# Incubator.net
KiCad netlist of a schematic drawn in EAGLE
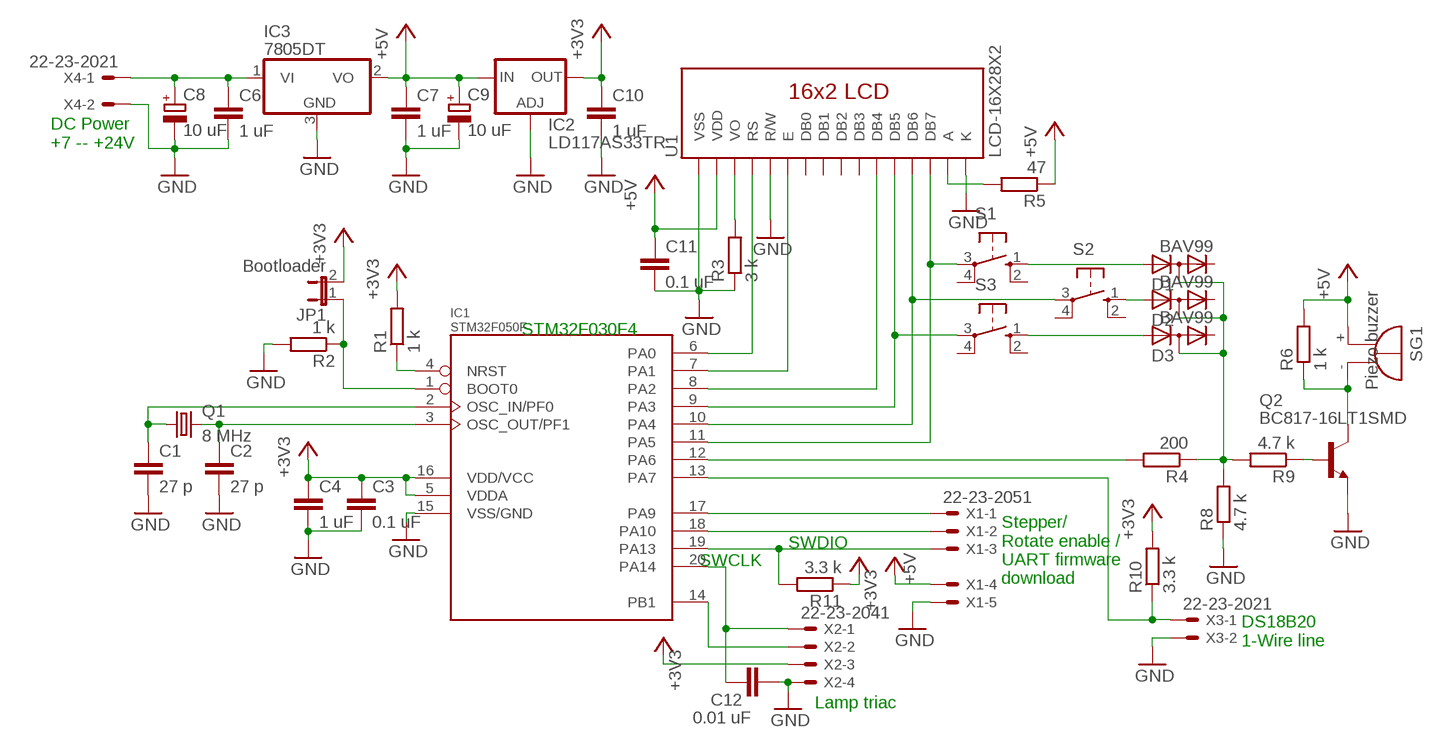
[diagram p0: schematic, sheet 1]

(export (version "E")
  (design (tool "Eeschema 10.0.6"))
  (components
    (comp (ref "C1")
      (value "27 p")
      (footprint "eagle-import:C0805")
      (libsource (lib "eagle-import") (part "C-EUC0805"))
    )
    (comp (ref "C2")
      (value "27 p")
      (footprint "eagle-import:C0805")
      (libsource (lib "eagle-import") (part "C-EUC0805"))
    )
    (comp (ref "C3")
      (value "0.1 uF")
      (footprint "eagle-import:C0805")
      (libsource (lib "eagle-import") (part "C-EUC0805"))
    )
    (comp (ref "C4")
      (value "1 uF")
      (footprint "eagle-import:C0805")
      (libsource (lib "eagle-import") (part "C-EUC0805"))
    )
    (comp (ref "C6")
      (value "1 uF")
      (footprint "eagle-import:C0805")
      (libsource (lib "eagle-import") (part "C-EUC0805"))
    )
    (comp (ref "C7")
      (value "1 uF")
      (footprint "eagle-import:C0805")
      (libsource (lib "eagle-import") (part "C-EUC0805"))
    )
    (comp (ref "C8")
      (value "10 uF")
      (footprint "eagle-import:TT2D4L")
      (libsource (lib "eagle-import") (part "CPOL-EUTT2D4L"))
    )
    (comp (ref "C9")
      (value "10 uF")
      (footprint "eagle-import:TT2D4L")
      (libsource (lib "eagle-import") (part "CPOL-EUTT2D4L"))
    )
    (comp (ref "C10")
      (value "1 uF")
      (footprint "eagle-import:C0805")
      (libsource (lib "eagle-import") (part "C-EUC0805"))
    )
    (comp (ref "C11")
      (value "0.1 uF")
      (footprint "eagle-import:C0805")
      (libsource (lib "eagle-import") (part "C-EUC0805"))
    )
    (comp (ref "C12")
      (value "0.01 uF")
      (footprint "eagle-import:C0805")
      (libsource (lib "eagle-import") (part "C-EUC0805"))
    )
    (comp (ref "D1")
      (value "BAV99")
      (footprint "eagle-import:SOT23")
      (libsource (lib "eagle-import") (part "BAV199"))
    )
    (comp (ref "D2")
      (value "BAV99")
      (footprint "eagle-import:SOT23")
      (libsource (lib "eagle-import") (part "BAV199"))
    )
    (comp (ref "D3")
      (value "BAV99")
      (footprint "eagle-import:SOT23")
      (libsource (lib "eagle-import") (part "BAV199"))
    )
    (comp (ref "IC1")
      (value "STM32F050F")
      (footprint "eagle-import:TSSOP20")
      (libsource (lib "eagle-import") (part "STM32F050F"))
    )
    (comp (ref "IC2")
      (value "LD117AS33TR")
      (footprint "eagle-import:SOT223")
      (libsource (lib "eagle-import") (part "LD117A?S33TR"))
    )
    (comp (ref "IC3")
      (value "7805DT")
      (footprint "eagle-import:TO252")
      (libsource (lib "eagle-import") (part "78DT05"))
    )
    (comp (ref "JP1")
      (value "Bootloader")
      (footprint "eagle-import:JP1")
      (libsource (lib "eagle-import") (part "JP1E"))
    )
    (comp (ref "Q1")
      (value "8 MHz")
      (footprint "eagle-import:HC49_S")
      (libsource (lib "eagle-import") (part "CRYSTALHC49S"))
    )
    (comp (ref "Q2")
      (value "BC817-16LT1SMD")
      (footprint "eagle-import:SOT23-BEC")
      (libsource (lib "eagle-import") (part "BC817SMD-16LT1"))
    )
    (comp (ref "R1")
      (value "1 k")
      (footprint "eagle-import:R0805")
      (libsource (lib "eagle-import") (part "R-EU_R0805"))
    )
    (comp (ref "R2")
      (value "1 k")
      (footprint "eagle-import:R0805")
      (libsource (lib "eagle-import") (part "R-EU_R0805"))
    )
    (comp (ref "R3")
      (value "3 k")
      (footprint "eagle-import:R0805")
      (libsource (lib "eagle-import") (part "R-EU_R0805"))
    )
    (comp (ref "R4")
      (value "200")
      (footprint "eagle-import:R0805")
      (libsource (lib "eagle-import") (part "R-EU_R0805"))
    )
    (comp (ref "R5")
      (value "47")
      (footprint "eagle-import:R0805")
      (libsource (lib "eagle-import") (part "R-EU_R0805"))
    )
    (comp (ref "R6")
      (value "1 k")
      (footprint "eagle-import:R0805")
      (libsource (lib "eagle-import") (part "R-EU_R0805"))
    )
    (comp (ref "R8")
      (value "4.7 k")
      (footprint "eagle-import:R0805")
      (libsource (lib "eagle-import") (part "R-EU_R0805"))
    )
    (comp (ref "R9")
      (value "4.7 k")
      (footprint "eagle-import:R0805")
      (libsource (lib "eagle-import") (part "R-EU_R0805"))
    )
    (comp (ref "R10")
      (value "3.3 k")
      (footprint "eagle-import:R0805")
      (libsource (lib "eagle-import") (part "R-EU_R0805"))
    )
    (comp (ref "R11")
      (value "3.3 k")
      (footprint "eagle-import:R0805")
      (libsource (lib "eagle-import") (part "R-EU_R0805"))
    )
    (comp (ref "S1")
      (value "10-XX")
      (footprint "eagle-import:B3F-10XX")
      (fields (field (name "MPN") "B3F-1000"))
      (libsource (lib "eagle-import") (part "10-XX"))
    )
    (comp (ref "S2")
      (value "10-XX")
      (footprint "eagle-import:B3F-10XX")
      (fields (field (name "MPN") "B3F-1000"))
      (libsource (lib "eagle-import") (part "10-XX"))
    )
    (comp (ref "S3")
      (value "10-XX")
      (footprint "eagle-import:B3F-10XX")
      (fields (field (name "MPN") "B3F-1000"))
      (libsource (lib "eagle-import") (part "10-XX"))
    )
    (comp (ref "SG1")
      (value "Piezo buzzer")
      (footprint "eagle-import:F_HMB")
      (libsource (lib "eagle-import") (part "F/HMB"))
    )
    (comp (ref "U1")
      (value "LCD-16X28X2")
      (footprint "eagle-import:LCD-8X2")
      (libsource (lib "eagle-import") (part "LCD-16X28X2"))
    )
    (comp (ref "X1")
      (value "22-23-2051")
      (footprint "eagle-import:22-23-2051")
      (fields (field (name "MF") "MOLEX"))
      (libsource (lib "eagle-import") (part "22-23-2051"))
    )
    (comp (ref "X2")
      (value "22-23-2041")
      (footprint "eagle-import:22-23-2041")
      (fields (field (name "MF") "MOLEX"))
      (libsource (lib "eagle-import") (part "22-23-2041"))
    )
    (comp (ref "X3")
      (value "22-23-2021")
      (footprint "eagle-import:22-23-2021")
      (fields (field (name "MF") "MOLEX"))
      (libsource (lib "eagle-import") (part "22-23-2021"))
    )
    (comp (ref "X4")
      (value "22-23-2021")
      (footprint "eagle-import:22-23-2021")
      (fields (field (name "MF") "MOLEX"))
      (libsource (lib "eagle-import") (part "22-23-2021"))
    )
  )
  (nets
    (net (code "1") (name "+3V3") (class "Default")
      (node (ref "C10") (pin "1") (pinfunction "1_1") (pintype "passive"))
      (node (ref "C3") (pin "1") (pinfunction "1_1") (pintype "passive"))
      (node (ref "C4") (pin "1") (pinfunction "1_1") (pintype "passive"))
      (node (ref "IC1") (pin "16") (pinfunction "VDD/VCC_16") (pintype "power_in"))
      (node (ref "IC1") (pin "5") (pinfunction "VDDA_5") (pintype "power_in"))
      (node (ref "IC2") (pin "4") (pinfunction "OUT_4") (pintype "passive"))
      (node (ref "JP1") (pin "2") (pinfunction "2_2") (pintype "passive"))
      (node (ref "R1") (pin "2") (pinfunction "2_2") (pintype "passive"))
      (node (ref "R10") (pin "2") (pinfunction "2_2") (pintype "passive"))
      (node (ref "R11") (pin "1") (pinfunction "1_1") (pintype "passive"))
      (node (ref "X2") (pin "3") (pinfunction "S_3") (pintype "passive"))
    )
    (net (code "2") (name "+5V") (class "Default")
      (node (ref "C11") (pin "1") (pinfunction "1_1") (pintype "passive"))
      (node (ref "C7") (pin "1") (pinfunction "1_1") (pintype "passive"))
      (node (ref "C9") (pin "+") (pinfunction "+_+") (pintype "passive"))
      (node (ref "IC2") (pin "3") (pinfunction "IN_3") (pintype "input"))
      (node (ref "IC3") (pin "2") (pinfunction "VO_2") (pintype "passive"))
      (node (ref "R5") (pin "1") (pinfunction "1_1") (pintype "passive"))
      (node (ref "R6") (pin "2") (pinfunction "2_2") (pintype "passive"))
      (node (ref "SG1") (pin "+") (pinfunction "+_+") (pintype "passive"))
      (node (ref "U1") (pin "2") (pinfunction "VDD_2") (pintype "power_in"))
      (node (ref "X1") (pin "4") (pinfunction "S_4") (pintype "passive"))
    )
    (net (code "3") (name "GND") (class "Default")
      (node (ref "C1") (pin "2") (pinfunction "2_2") (pintype "passive"))
      (node (ref "C10") (pin "2") (pinfunction "2_2") (pintype "passive"))
      (node (ref "C11") (pin "2") (pinfunction "2_2") (pintype "passive"))
      (node (ref "C12") (pin "2") (pinfunction "2_2") (pintype "passive"))
      (node (ref "C2") (pin "2") (pinfunction "2_2") (pintype "passive"))
      (node (ref "C3") (pin "2") (pinfunction "2_2") (pintype "passive"))
      (node (ref "C4") (pin "2") (pinfunction "2_2") (pintype "passive"))
      (node (ref "C6") (pin "2") (pinfunction "2_2") (pintype "passive"))
      (node (ref "C7") (pin "2") (pinfunction "2_2") (pintype "passive"))
      (node (ref "C8") (pin "-") (pinfunction "-_-") (pintype "passive"))
      (node (ref "C9") (pin "-") (pinfunction "-_-") (pintype "passive"))
      (node (ref "IC1") (pin "15") (pinfunction "VSS/GND_15") (pintype "power_in"))
      (node (ref "IC2") (pin "1") (pinfunction "ADJ_1") (pintype "input"))
      (node (ref "IC3") (pin "3") (pinfunction "GND_3") (pintype "passive"))
      (node (ref "Q2") (pin "E") (pinfunction "E_E") (pintype "passive"))
      (node (ref "R2") (pin "2") (pinfunction "2_2") (pintype "passive"))
      (node (ref "R3") (pin "1") (pinfunction "1_1") (pintype "passive"))
      (node (ref "R8") (pin "1") (pinfunction "1_1") (pintype "passive"))
      (node (ref "U1") (pin "1") (pinfunction "VSS_1") (pintype "power_in"))
      (node (ref "U1") (pin "16") (pinfunction "K_16") (pintype "power_in"))
      (node (ref "U1") (pin "5") (pinfunction "R/W_5") (pintype "input"))
      (node (ref "X1") (pin "5") (pinfunction "S_5") (pintype "passive"))
      (node (ref "X2") (pin "4") (pinfunction "S_4") (pintype "passive"))
      (node (ref "X3") (pin "2") (pinfunction "S_2") (pintype "passive"))
      (node (ref "X4") (pin "2") (pinfunction "S_2") (pintype "passive"))
    )
    (net (code "4") (name "Net-(D1-A)") (class "Default")
      (node (ref "D1") (pin "1") (pinfunction "A_1") (pintype "passive"))
      (node (ref "S1") (pin "1") (pinfunction "S_1") (pintype "passive"))
    )
    (net (code "5") (name "Net-(D1-AC)") (class "Default")
      (node (ref "D1") (pin "3") (pinfunction "AC_3") (pintype "passive"))
      (node (ref "D2") (pin "3") (pinfunction "AC_3") (pintype "passive"))
      (node (ref "D3") (pin "3") (pinfunction "AC_3") (pintype "passive"))
      (node (ref "R4") (pin "1") (pinfunction "1_1") (pintype "passive"))
      (node (ref "R8") (pin "2") (pinfunction "2_2") (pintype "passive"))
      (node (ref "R9") (pin "2") (pinfunction "2_2") (pintype "passive"))
    )
    (net (code "6") (name "Net-(D2-A)") (class "Default")
      (node (ref "D2") (pin "1") (pinfunction "A_1") (pintype "passive"))
      (node (ref "S2") (pin "1") (pinfunction "S_1") (pintype "passive"))
    )
    (net (code "7") (name "Net-(D3-A)") (class "Default")
      (node (ref "D3") (pin "1") (pinfunction "A_1") (pintype "passive"))
      (node (ref "S3") (pin "1") (pinfunction "S_1") (pintype "passive"))
    )
    (net (code "8") (name "Net-(IC1-BOOT0)") (class "Default")
      (node (ref "IC1") (pin "1") (pinfunction "BOOT0_1") (pintype "bidirectional"))
      (node (ref "JP1") (pin "1") (pinfunction "1_1") (pintype "passive"))
      (node (ref "R2") (pin "1") (pinfunction "1_1") (pintype "passive"))
    )
    (net (code "9") (name "Net-(IC1-NRST)") (class "Default")
      (node (ref "IC1") (pin "4") (pinfunction "NRST_4") (pintype "bidirectional"))
      (node (ref "R1") (pin "1") (pinfunction "1_1") (pintype "passive"))
    )
    (net (code "10") (name "Net-(IC1-OSC_IN{slash}PF0)") (class "Default")
      (node (ref "C1") (pin "1") (pinfunction "1_1") (pintype "passive"))
      (node (ref "IC1") (pin "2") (pinfunction "OSC_IN/PF0_2") (pintype "bidirectional"))
      (node (ref "Q1") (pin "1") (pinfunction "1_1") (pintype "passive"))
    )
    (net (code "11") (name "Net-(IC1-OSC_OUT{slash}PF1)") (class "Default")
      (node (ref "C2") (pin "1") (pinfunction "1_1") (pintype "passive"))
      (node (ref "IC1") (pin "3") (pinfunction "OSC_OUT/PF1_3") (pintype "bidirectional"))
      (node (ref "Q1") (pin "2") (pinfunction "2_2") (pintype "passive"))
    )
    (net (code "12") (name "Net-(IC1-PA0)") (class "Default")
      (node (ref "IC1") (pin "6") (pinfunction "PA0_6") (pintype "bidirectional"))
      (node (ref "U1") (pin "4") (pinfunction "RS_4") (pintype "input"))
    )
    (net (code "13") (name "Net-(IC1-PA1)") (class "Default")
      (node (ref "IC1") (pin "7") (pinfunction "PA1_7") (pintype "bidirectional"))
      (node (ref "U1") (pin "6") (pinfunction "E_6") (pintype "input"))
    )
    (net (code "14") (name "Net-(IC1-PA2)") (class "Default")
      (node (ref "IC1") (pin "8") (pinfunction "PA2_8") (pintype "bidirectional"))
      (node (ref "U1") (pin "11") (pinfunction "DB4_11") (pintype "bidirectional"))
    )
    (net (code "15") (name "Net-(IC1-PA3)") (class "Default")
      (node (ref "IC1") (pin "9") (pinfunction "PA3_9") (pintype "bidirectional"))
      (node (ref "S3") (pin "3") (pinfunction "P_3") (pintype "passive"))
      (node (ref "U1") (pin "12") (pinfunction "DB5_12") (pintype "bidirectional"))
    )
    (net (code "16") (name "Net-(IC1-PA4)") (class "Default")
      (node (ref "IC1") (pin "10") (pinfunction "PA4_10") (pintype "bidirectional"))
      (node (ref "S2") (pin "3") (pinfunction "P_3") (pintype "passive"))
      (node (ref "U1") (pin "13") (pinfunction "DB6_13") (pintype "bidirectional"))
    )
    (net (code "17") (name "Net-(IC1-PA5)") (class "Default")
      (node (ref "IC1") (pin "11") (pinfunction "PA5_11") (pintype "bidirectional"))
      (node (ref "S1") (pin "3") (pinfunction "P_3") (pintype "passive"))
      (node (ref "U1") (pin "14") (pinfunction "DB7_14") (pintype "bidirectional"))
    )
    (net (code "18") (name "Net-(IC1-PA6)") (class "Default")
      (node (ref "IC1") (pin "12") (pinfunction "PA6_12") (pintype "bidirectional"))
      (node (ref "R4") (pin "2") (pinfunction "2_2") (pintype "passive"))
    )
    (net (code "19") (name "Net-(IC1-PA7)") (class "Default")
      (node (ref "IC1") (pin "13") (pinfunction "PA7_13") (pintype "bidirectional"))
      (node (ref "R10") (pin "1") (pinfunction "1_1") (pintype "passive"))
      (node (ref "X3") (pin "1") (pinfunction "S_1") (pintype "passive"))
    )
    (net (code "20") (name "Net-(IC1-PA9)") (class "Default")
      (node (ref "IC1") (pin "17") (pinfunction "PA9_17") (pintype "bidirectional"))
      (node (ref "X1") (pin "1") (pinfunction "S_1") (pintype "passive"))
    )
    (net (code "21") (name "Net-(IC1-PA10)") (class "Default")
      (node (ref "IC1") (pin "18") (pinfunction "PA10_18") (pintype "bidirectional"))
      (node (ref "X1") (pin "2") (pinfunction "S_2") (pintype "passive"))
    )
    (net (code "22") (name "Net-(IC1-PA13)") (class "Default")
      (node (ref "IC1") (pin "19") (pinfunction "PA13_19") (pintype "bidirectional"))
      (node (ref "R11") (pin "2") (pinfunction "2_2") (pintype "passive"))
      (node (ref "X1") (pin "3") (pinfunction "S_3") (pintype "passive"))
    )
    (net (code "23") (name "Net-(IC1-PA14)") (class "Default")
      (node (ref "C12") (pin "1") (pinfunction "1_1") (pintype "passive"))
      (node (ref "IC1") (pin "20") (pinfunction "PA14_20") (pintype "bidirectional"))
      (node (ref "X2") (pin "1") (pinfunction "S_1") (pintype "passive"))
    )
    (net (code "24") (name "Net-(IC1-PB1)") (class "Default")
      (node (ref "IC1") (pin "14") (pinfunction "PB1_14") (pintype "bidirectional"))
      (node (ref "X2") (pin "2") (pinfunction "S_2") (pintype "passive"))
    )
    (net (code "25") (name "Net-(IC3-VI)") (class "Default")
      (node (ref "C6") (pin "1") (pinfunction "1_1") (pintype "passive"))
      (node (ref "C8") (pin "+") (pinfunction "+_+") (pintype "passive"))
      (node (ref "IC3") (pin "1") (pinfunction "VI_1") (pintype "input"))
      (node (ref "X4") (pin "1") (pinfunction "S_1") (pintype "passive"))
    )
    (net (code "26") (name "Net-(Q2-PadB)") (class "Default")
      (node (ref "Q2") (pin "B") (pinfunction "B_B") (pintype "passive"))
      (node (ref "R9") (pin "1") (pinfunction "1_1") (pintype "passive"))
    )
    (net (code "27") (name "Net-(Q2-PadC)") (class "Default")
      (node (ref "Q2") (pin "C") (pinfunction "C_C") (pintype "passive"))
      (node (ref "R6") (pin "1") (pinfunction "1_1") (pintype "passive"))
      (node (ref "SG1") (pin "-") (pinfunction "-_-") (pintype "passive"))
    )
    (net (code "28") (name "Net-(U1-A)") (class "Default")
      (node (ref "R5") (pin "2") (pinfunction "2_2") (pintype "passive"))
      (node (ref "U1") (pin "15") (pinfunction "A_15") (pintype "power_in"))
    )
    (net (code "29") (name "Net-(U1-VO)") (class "Default")
      (node (ref "R3") (pin "2") (pinfunction "2_2") (pintype "passive"))
      (node (ref "U1") (pin "3") (pinfunction "VO_3") (pintype "bidirectional"))
    )
    (net (code "30") (name "unconnected-(D1-C-Pad2)") (class "Default")
      (node (ref "D1") (pin "2") (pinfunction "C_2") (pintype "passive"))
    )
    (net (code "31") (name "unconnected-(D2-C-Pad2)") (class "Default")
      (node (ref "D2") (pin "2") (pinfunction "C_2") (pintype "passive"))
    )
    (net (code "32") (name "unconnected-(D3-C-Pad2)") (class "Default")
      (node (ref "D3") (pin "2") (pinfunction "C_2") (pintype "passive"))
    )
    (net (code "33") (name "unconnected-(S1-P1-Pad4)") (class "Default")
      (node (ref "S1") (pin "4") (pinfunction "P1_4") (pintype "passive"))
    )
    (net (code "34") (name "unconnected-(S1-S1-Pad2)") (class "Default")
      (node (ref "S1") (pin "2") (pinfunction "S1_2") (pintype "passive"))
    )
    (net (code "35") (name "unconnected-(S2-P1-Pad4)") (class "Default")
      (node (ref "S2") (pin "4") (pinfunction "P1_4") (pintype "passive"))
    )
    (net (code "36") (name "unconnected-(S2-S1-Pad2)") (class "Default")
      (node (ref "S2") (pin "2") (pinfunction "S1_2") (pintype "passive"))
    )
    (net (code "37") (name "unconnected-(S3-P1-Pad4)") (class "Default")
      (node (ref "S3") (pin "4") (pinfunction "P1_4") (pintype "passive"))
    )
    (net (code "38") (name "unconnected-(S3-S1-Pad2)") (class "Default")
      (node (ref "S3") (pin "2") (pinfunction "S1_2") (pintype "passive"))
    )
    (net (code "39") (name "unconnected-(U1-DB0-Pad7)") (class "Default")
      (node (ref "U1") (pin "7") (pinfunction "DB0_7") (pintype "bidirectional"))
    )
    (net (code "40") (name "unconnected-(U1-DB1-Pad8)") (class "Default")
      (node (ref "U1") (pin "8") (pinfunction "DB1_8") (pintype "bidirectional"))
    )
    (net (code "41") (name "unconnected-(U1-DB2-Pad9)") (class "Default")
      (node (ref "U1") (pin "9") (pinfunction "DB2_9") (pintype "bidirectional"))
    )
    (net (code "42") (name "unconnected-(U1-DB3-Pad10)") (class "Default")
      (node (ref "U1") (pin "10") (pinfunction "DB3_10") (pintype "bidirectional"))
    )
  )
)
